# PCB-RS422_485-DB9.net
KiCad netlist of a schematic drawn in EAGLE
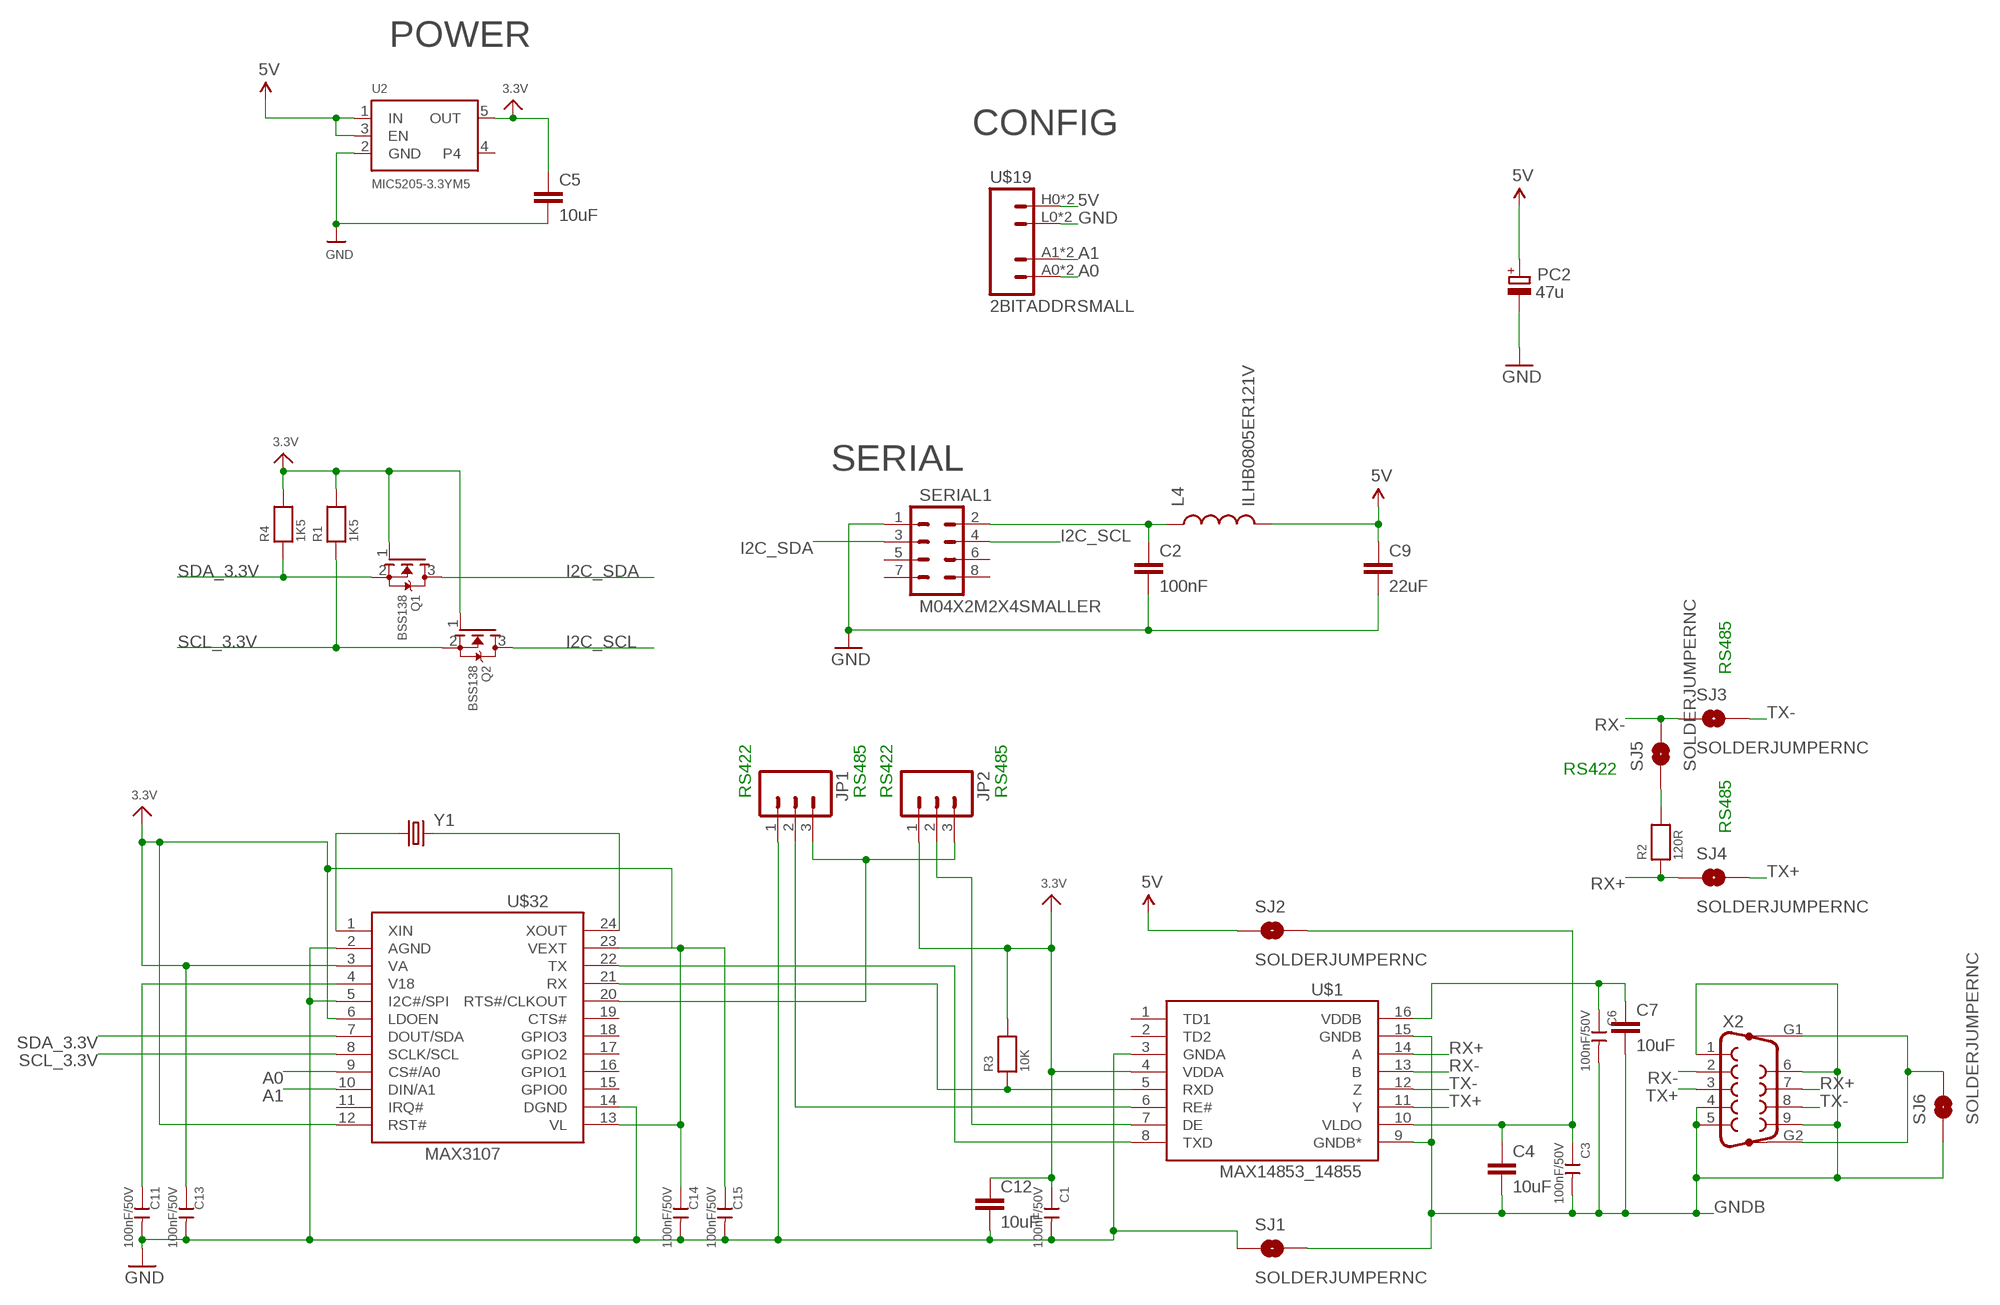
[diagram p0: schematic, sheet 1]

(export (version "E")
  (design (tool "Eeschema 10.0.6"))
  (components
    (comp (ref "C1")
      (value "100nF/50V")
      (footprint "eagle-import:C0603")
      (libsource (lib "eagle-import") (part "CAP-0603"))
    )
    (comp (ref "C2")
      (value "100nF")
      (footprint "eagle-import:0603-CAP")
      (libsource (lib "eagle-import") (part "CAP0603-CAP"))
    )
    (comp (ref "C3")
      (value "100nF/50V")
      (footprint "eagle-import:C0603")
      (libsource (lib "eagle-import") (part "CAP-0603"))
    )
    (comp (ref "C4")
      (value "10uF")
      (footprint "eagle-import:0805")
      (libsource (lib "eagle-import") (part "CAP0805"))
    )
    (comp (ref "C5")
      (value "10uF")
      (footprint "eagle-import:0805")
      (libsource (lib "eagle-import") (part "CAP0805"))
    )
    (comp (ref "C6")
      (value "100nF/50V")
      (footprint "eagle-import:C0603")
      (libsource (lib "eagle-import") (part "CAP-0603"))
    )
    (comp (ref "C7")
      (value "10uF")
      (footprint "eagle-import:0805")
      (libsource (lib "eagle-import") (part "CAP0805"))
    )
    (comp (ref "C9")
      (value "22uF")
      (footprint "eagle-import:0805")
      (libsource (lib "eagle-import") (part "CAP0805"))
    )
    (comp (ref "C11")
      (value "100nF/50V")
      (footprint "eagle-import:C0603")
      (libsource (lib "eagle-import") (part "CAP-0603"))
    )
    (comp (ref "C12")
      (value "10uF")
      (footprint "eagle-import:0805")
      (libsource (lib "eagle-import") (part "CAP0805"))
    )
    (comp (ref "C13")
      (value "100nF/50V")
      (footprint "eagle-import:C0603")
      (libsource (lib "eagle-import") (part "CAP-0603"))
    )
    (comp (ref "C14")
      (value "100nF/50V")
      (footprint "eagle-import:C0603")
      (libsource (lib "eagle-import") (part "CAP-0603"))
    )
    (comp (ref "C15")
      (value "100nF/50V")
      (footprint "eagle-import:C0603")
      (libsource (lib "eagle-import") (part "CAP-0603"))
    )
    (comp (ref "JP1")
      (value "M03LOCK")
      (footprint "eagle-import:1X03_LOCK")
      (libsource (lib "eagle-import") (part "M03LOCK"))
    )
    (comp (ref "JP2")
      (value "M03LOCK")
      (footprint "eagle-import:1X03_LOCK")
      (libsource (lib "eagle-import") (part "M03LOCK"))
    )
    (comp (ref "L4")
      (value "ILHB0805ER121V")
      (footprint "eagle-import:0805")
      (libsource (lib "eagle-import") (part "INDUCTOR0805"))
    )
    (comp (ref "PC2")
      (value "47u")
      (footprint "eagle-import:PANASONIC_D")
      (libsource (lib "eagle-import") (part "CPOL-EUD"))
    )
    (comp (ref "Q1")
      (value "BSS138")
      (footprint "eagle-import:SOT23-R")
      (libsource (lib "eagle-import") (part "MOSFET-NREFLOW"))
    )
    (comp (ref "Q2")
      (value "BSS138")
      (footprint "eagle-import:SOT23-R")
      (libsource (lib "eagle-import") (part "MOSFET-NREFLOW"))
    )
    (comp (ref "R1")
      (value "1K5")
      (footprint "eagle-import:0603")
      (libsource (lib "eagle-import") (part "RESISTOR0603"))
    )
    (comp (ref "R2")
      (value "120R")
      (footprint "eagle-import:0603")
      (libsource (lib "eagle-import") (part "RESISTOR0603"))
    )
    (comp (ref "R3")
      (value "10K")
      (footprint "eagle-import:0603")
      (libsource (lib "eagle-import") (part "RESISTOR0603"))
    )
    (comp (ref "R4")
      (value "1K5")
      (footprint "eagle-import:0603")
      (libsource (lib "eagle-import") (part "RESISTOR0603"))
    )
    (comp (ref "SERIAL1")
      (value "M04X2M2X4SMALLER")
      (footprint "eagle-import:M2X4SMALLER")
      (libsource (lib "eagle-import") (part "M04X2M2X4SMALLER"))
    )
    (comp (ref "SJ1")
      (value "SOLDERJUMPERNC")
      (footprint "eagle-import:SJ_2S")
      (libsource (lib "eagle-import") (part "SOLDERJUMPERNC"))
    )
    (comp (ref "SJ2")
      (value "SOLDERJUMPERNC")
      (footprint "eagle-import:SJ_2S")
      (libsource (lib "eagle-import") (part "SOLDERJUMPERNC"))
    )
    (comp (ref "SJ3")
      (value "SOLDERJUMPERNC")
      (footprint "eagle-import:SJ_2S")
      (libsource (lib "eagle-import") (part "SOLDERJUMPERNC"))
    )
    (comp (ref "SJ4")
      (value "SOLDERJUMPERNC")
      (footprint "eagle-import:SJ_2S")
      (libsource (lib "eagle-import") (part "SOLDERJUMPERNC"))
    )
    (comp (ref "SJ5")
      (value "SOLDERJUMPERNC")
      (footprint "eagle-import:SJ_2S")
      (libsource (lib "eagle-import") (part "SOLDERJUMPERNC"))
    )
    (comp (ref "SJ6")
      (value "SOLDERJUMPERNC")
      (footprint "eagle-import:SJ_2S")
      (libsource (lib "eagle-import") (part "SOLDERJUMPERNC"))
    )
    (comp (ref "U$1")
      (value "MAX14853_14855")
      (footprint "eagle-import:SO-16W")
      (libsource (lib "eagle-import") (part "MAX14853_14855"))
    )
    (comp (ref "U$19")
      (value "2BITADDRSMALL")
      (footprint "eagle-import:2BITADDR_SMALL")
      (libsource (lib "eagle-import") (part "2BITADDRSMALL"))
    )
    (comp (ref "U$32")
      (value "MAX3107")
      (footprint "eagle-import:SSOP24")
      (libsource (lib "eagle-import") (part "MAX3107"))
    )
    (comp (ref "U2")
      (value "MIC5205-3.3YM5")
      (footprint "eagle-import:SOT23-5")
      (libsource (lib "eagle-import") (part "VREG_SOT23-5"))
    )
    (comp (ref "X2")
      (value "F09HP")
      (footprint "eagle-import:F09HP")
      (libsource (lib "eagle-import") (part "F09HP"))
    )
    (comp (ref "Y1")
      (value "CRYSTALHC49US")
      (footprint "eagle-import:HC49US")
      (libsource (lib "eagle-import") (part "CRYSTALHC49US"))
    )
  )
  (nets
    (net (code "1") (name "3.3V") (class "Default")
      (node (ref "C1") (pin "1") (pinfunction "1_1") (pintype "passive"))
      (node (ref "C12") (pin "1") (pinfunction "1_1") (pintype "passive"))
      (node (ref "C13") (pin "1") (pinfunction "1_1") (pintype "passive"))
      (node (ref "C14") (pin "1") (pinfunction "1_1") (pintype "passive"))
      (node (ref "C15") (pin "1") (pinfunction "1_1") (pintype "passive"))
      (node (ref "C5") (pin "1") (pinfunction "1_1") (pintype "passive"))
      (node (ref "JP2") (pin "1") (pinfunction "1_1") (pintype "passive"))
      (node (ref "Q1") (pin "1") (pinfunction "G_1") (pintype "bidirectional"))
      (node (ref "Q2") (pin "1") (pinfunction "G_1") (pintype "bidirectional"))
      (node (ref "R1") (pin "2") (pinfunction "2_2") (pintype "passive"))
      (node (ref "R3") (pin "2") (pinfunction "2_2") (pintype "passive"))
      (node (ref "R4") (pin "2") (pinfunction "2_2") (pintype "passive"))
      (node (ref "U$1") (pin "4") (pinfunction "VDDA_4") (pintype "power_in"))
      (node (ref "U$32") (pin "12") (pinfunction "RST#_12") (pintype "input"))
      (node (ref "U$32") (pin "13") (pinfunction "VL_13") (pintype "power_in"))
      (node (ref "U$32") (pin "23") (pinfunction "VEXT_23") (pintype "power_in"))
      (node (ref "U$32") (pin "3") (pinfunction "VA_3") (pintype "power_in"))
      (node (ref "U$32") (pin "6") (pinfunction "LDOEN_6") (pintype "input"))
      (node (ref "U2") (pin "5") (pinfunction "OUT_5") (pintype "bidirectional"))
    )
    (net (code "2") (name "5V") (class "Default")
      (node (ref "C9") (pin "1") (pinfunction "1_1") (pintype "passive"))
      (node (ref "L4") (pin "2") (pinfunction "2_2") (pintype "passive"))
      (node (ref "PC2") (pin "+") (pinfunction "+_+") (pintype "passive"))
      (node (ref "SJ2") (pin "1") (pinfunction "1_1") (pintype "passive"))
      (node (ref "U$19") (pin "H0") (pinfunction "VCC_H0") (pintype "passive"))
      (node (ref "U$19") (pin "H1") (pinfunction "VCC_H1") (pintype "passive"))
      (node (ref "U2") (pin "1") (pinfunction "IN_1") (pintype "bidirectional"))
      (node (ref "U2") (pin "3") (pinfunction "EN_3") (pintype "bidirectional"))
    )
    (net (code "3") (name "A0") (class "Default")
      (node (ref "U$19") (pin "A0") (pinfunction "A1_A0") (pintype "passive"))
      (node (ref "U$19") (pin "AS0") (pinfunction "A1_AS0") (pintype "passive"))
      (node (ref "U$32") (pin "9") (pinfunction "CS#/A0_9") (pintype "input"))
    )
    (net (code "4") (name "A1") (class "Default")
      (node (ref "U$19") (pin "A1") (pinfunction "A2_A1") (pintype "passive"))
      (node (ref "U$19") (pin "AS1") (pinfunction "A2_AS1") (pintype "passive"))
      (node (ref "U$32") (pin "10") (pinfunction "DIN/A1_10") (pintype "input"))
    )
    (net (code "5") (name "GND") (class "Default")
      (node (ref "C1") (pin "2") (pinfunction "2_2") (pintype "passive"))
      (node (ref "C11") (pin "2") (pinfunction "2_2") (pintype "passive"))
      (node (ref "C12") (pin "2") (pinfunction "2_2") (pintype "passive"))
      (node (ref "C13") (pin "2") (pinfunction "2_2") (pintype "passive"))
      (node (ref "C14") (pin "2") (pinfunction "2_2") (pintype "passive"))
      (node (ref "C15") (pin "2") (pinfunction "2_2") (pintype "passive"))
      (node (ref "C2") (pin "2") (pinfunction "2_2") (pintype "passive"))
      (node (ref "C5") (pin "2") (pinfunction "2_2") (pintype "passive"))
      (node (ref "C9") (pin "2") (pinfunction "2_2") (pintype "passive"))
      (node (ref "JP1") (pin "1") (pinfunction "1_1") (pintype "passive"))
      (node (ref "PC2") (pin "-") (pinfunction "-_-") (pintype "passive"))
      (node (ref "SERIAL1") (pin "1") (pinfunction "1_1") (pintype "passive"))
      (node (ref "SJ1") (pin "1") (pinfunction "1_1") (pintype "passive"))
      (node (ref "U$1") (pin "3") (pinfunction "GNDA_3") (pintype "power_in"))
      (node (ref "U$19") (pin "L0") (pinfunction "GND_L0") (pintype "passive"))
      (node (ref "U$19") (pin "L1") (pinfunction "GND_L1") (pintype "passive"))
      (node (ref "U$32") (pin "14") (pinfunction "DGND_14") (pintype "power_in"))
      (node (ref "U$32") (pin "2") (pinfunction "AGND_2") (pintype "power_in"))
      (node (ref "U$32") (pin "5") (pinfunction "I2C#/SPI_5") (pintype "input"))
      (node (ref "U2") (pin "2") (pinfunction "GND_2") (pintype "bidirectional"))
    )
    (net (code "6") (name "GNDB") (class "Default")
      (node (ref "C3") (pin "2") (pinfunction "2_2") (pintype "passive"))
      (node (ref "C4") (pin "2") (pinfunction "2_2") (pintype "passive"))
      (node (ref "C6") (pin "2") (pinfunction "2_2") (pintype "passive"))
      (node (ref "C7") (pin "2") (pinfunction "2_2") (pintype "passive"))
      (node (ref "SJ1") (pin "2") (pinfunction "2_2") (pintype "passive"))
      (node (ref "SJ6") (pin "1") (pinfunction "1_1") (pintype "passive"))
      (node (ref "U$1") (pin "15") (pinfunction "GNDB_15") (pintype "power_in"))
      (node (ref "U$1") (pin "9") (pinfunction "GNDB*_9") (pintype "power_in"))
      (node (ref "X2") (pin "1") (pinfunction "1_1") (pintype "passive"))
      (node (ref "X2") (pin "4") (pinfunction "4_4") (pintype "passive"))
      (node (ref "X2") (pin "5") (pinfunction "5_5") (pintype "passive"))
      (node (ref "X2") (pin "6") (pinfunction "6_6") (pintype "passive"))
      (node (ref "X2") (pin "9") (pinfunction "9_9") (pintype "passive"))
    )
    (net (code "7") (name "I2C_SCL") (class "Default")
      (node (ref "Q2") (pin "3") (pinfunction "D_3") (pintype "bidirectional"))
      (node (ref "SERIAL1") (pin "4") (pinfunction "4_4") (pintype "passive"))
    )
    (net (code "8") (name "I2C_SDA") (class "Default")
      (node (ref "Q1") (pin "3") (pinfunction "D_3") (pintype "bidirectional"))
      (node (ref "SERIAL1") (pin "3") (pinfunction "3_3") (pintype "passive"))
    )
    (net (code "9") (name "Net-(C2-Pad1)") (class "Default")
      (node (ref "C2") (pin "1") (pinfunction "1_1") (pintype "passive"))
      (node (ref "L4") (pin "1") (pinfunction "1_1") (pintype "passive"))
      (node (ref "SERIAL1") (pin "2") (pinfunction "2_2") (pintype "passive"))
    )
    (net (code "10") (name "Net-(R2-Pad2)") (class "Default")
      (node (ref "R2") (pin "2") (pinfunction "2_2") (pintype "passive"))
      (node (ref "SJ5") (pin "1") (pinfunction "1_1") (pintype "passive"))
    )
    (net (code "11") (name "Net-(SJ6-Pad2)") (class "Default")
      (node (ref "SJ6") (pin "2") (pinfunction "2_2") (pintype "passive"))
      (node (ref "X2") (pin "G1") (pinfunction "G1_G1") (pintype "passive"))
      (node (ref "X2") (pin "G2") (pinfunction "G2_G2") (pintype "passive"))
    )
    (net (code "12") (name "Net-(U$1-DE)") (class "Default")
      (node (ref "JP2") (pin "2") (pinfunction "2_2") (pintype "passive"))
      (node (ref "U$1") (pin "7") (pinfunction "DE_7") (pintype "input"))
    )
    (net (code "13") (name "Net-(U$1-RE#)") (class "Default")
      (node (ref "JP1") (pin "2") (pinfunction "2_2") (pintype "passive"))
      (node (ref "U$1") (pin "6") (pinfunction "RE#_6") (pintype "input"))
    )
    (net (code "14") (name "Net-(U$1-RXD)") (class "Default")
      (node (ref "R3") (pin "1") (pinfunction "1_1") (pintype "passive"))
      (node (ref "U$1") (pin "5") (pinfunction "RXD_5") (pintype "output"))
      (node (ref "U$32") (pin "21") (pinfunction "RX_21") (pintype "input"))
    )
    (net (code "15") (name "Net-(U$1-TXD)") (class "Default")
      (node (ref "U$1") (pin "8") (pinfunction "TXD_8") (pintype "input"))
      (node (ref "U$32") (pin "22") (pinfunction "TX_22") (pintype "output"))
    )
    (net (code "16") (name "Net-(U$1-VDDB)") (class "Default")
      (node (ref "C6") (pin "1") (pinfunction "1_1") (pintype "passive"))
      (node (ref "C7") (pin "1") (pinfunction "1_1") (pintype "passive"))
      (node (ref "U$1") (pin "16") (pinfunction "VDDB_16") (pintype "output"))
    )
    (net (code "17") (name "Net-(U$1-VLDO)") (class "Default")
      (node (ref "C3") (pin "1") (pinfunction "1_1") (pintype "passive"))
      (node (ref "C4") (pin "1") (pinfunction "1_1") (pintype "passive"))
      (node (ref "SJ2") (pin "2") (pinfunction "2_2") (pintype "passive"))
      (node (ref "U$1") (pin "10") (pinfunction "VLDO_10") (pintype "power_in"))
    )
    (net (code "18") (name "Net-(U$32-RTS#{slash}CLKOUT)") (class "Default")
      (node (ref "JP1") (pin "3") (pinfunction "3_3") (pintype "passive"))
      (node (ref "JP2") (pin "3") (pinfunction "3_3") (pintype "passive"))
      (node (ref "U$32") (pin "20") (pinfunction "RTS#/CLKOUT_20") (pintype "bidirectional"))
    )
    (net (code "19") (name "Net-(U$32-V18)") (class "Default")
      (node (ref "C11") (pin "1") (pinfunction "1_1") (pintype "passive"))
      (node (ref "U$32") (pin "4") (pinfunction "V18_4") (pintype "output"))
    )
    (net (code "20") (name "Net-(U$32-XIN)") (class "Default")
      (node (ref "U$32") (pin "1") (pinfunction "XIN_1") (pintype "bidirectional"))
      (node (ref "Y1") (pin "1") (pinfunction "1_1") (pintype "passive"))
    )
    (net (code "21") (name "Net-(U$32-XOUT)") (class "Default")
      (node (ref "U$32") (pin "24") (pinfunction "XOUT_24") (pintype "bidirectional"))
      (node (ref "Y1") (pin "2") (pinfunction "2_2") (pintype "passive"))
    )
    (net (code "22") (name "RX+") (class "Default")
      (node (ref "R2") (pin "1") (pinfunction "1_1") (pintype "passive"))
      (node (ref "SJ4") (pin "1") (pinfunction "1_1") (pintype "passive"))
      (node (ref "U$1") (pin "14") (pinfunction "A_14") (pintype "input"))
      (node (ref "X2") (pin "7") (pinfunction "7_7") (pintype "passive"))
    )
    (net (code "23") (name "RX-") (class "Default")
      (node (ref "SJ3") (pin "1") (pinfunction "1_1") (pintype "passive"))
      (node (ref "SJ5") (pin "2") (pinfunction "2_2") (pintype "passive"))
      (node (ref "U$1") (pin "13") (pinfunction "B_13") (pintype "input"))
      (node (ref "X2") (pin "2") (pinfunction "2_2") (pintype "passive"))
    )
    (net (code "24") (name "SCL_3.3V") (class "Default")
      (node (ref "Q2") (pin "2") (pinfunction "S_2") (pintype "bidirectional"))
      (node (ref "R1") (pin "1") (pinfunction "1_1") (pintype "passive"))
      (node (ref "U$32") (pin "8") (pinfunction "SCLK/SCL_8") (pintype "input"))
    )
    (net (code "25") (name "SDA_3.3V") (class "Default")
      (node (ref "Q1") (pin "2") (pinfunction "S_2") (pintype "bidirectional"))
      (node (ref "R4") (pin "1") (pinfunction "1_1") (pintype "passive"))
      (node (ref "U$32") (pin "7") (pinfunction "DOUT/SDA_7") (pintype "bidirectional"))
    )
    (net (code "26") (name "TX+") (class "Default")
      (node (ref "SJ4") (pin "2") (pinfunction "2_2") (pintype "passive"))
      (node (ref "U$1") (pin "11") (pinfunction "Y_11") (pintype "output"))
      (node (ref "X2") (pin "3") (pinfunction "3_3") (pintype "passive"))
    )
    (net (code "27") (name "TX-") (class "Default")
      (node (ref "SJ3") (pin "2") (pinfunction "2_2") (pintype "passive"))
      (node (ref "U$1") (pin "12") (pinfunction "Z_12") (pintype "output"))
      (node (ref "X2") (pin "8") (pinfunction "8_8") (pintype "passive"))
    )
    (net (code "28") (name "unconnected-(SERIAL1-Pad5)") (class "Default")
      (node (ref "SERIAL1") (pin "5") (pinfunction "5_5") (pintype "passive"))
    )
    (net (code "29") (name "unconnected-(SERIAL1-Pad6)") (class "Default")
      (node (ref "SERIAL1") (pin "6") (pinfunction "6_6") (pintype "passive"))
    )
    (net (code "30") (name "unconnected-(SERIAL1-Pad7)") (class "Default")
      (node (ref "SERIAL1") (pin "7") (pinfunction "7_7") (pintype "passive"))
    )
    (net (code "31") (name "unconnected-(SERIAL1-Pad8)") (class "Default")
      (node (ref "SERIAL1") (pin "8") (pinfunction "8_8") (pintype "passive"))
    )
    (net (code "32") (name "unconnected-(U$1-TD1-Pad1)") (class "Default")
      (node (ref "U$1") (pin "1") (pinfunction "TD1_1") (pintype "output"))
    )
    (net (code "33") (name "unconnected-(U$1-TD2-Pad2)") (class "Default")
      (node (ref "U$1") (pin "2") (pinfunction "TD2_2") (pintype "output"))
    )
    (net (code "34") (name "unconnected-(U$32-CTS#-Pad19)") (class "Default")
      (node (ref "U$32") (pin "19") (pinfunction "CTS#_19") (pintype "bidirectional"))
    )
    (net (code "35") (name "unconnected-(U$32-GPIO0-Pad15)") (class "Default")
      (node (ref "U$32") (pin "15") (pinfunction "GPIO0_15") (pintype "bidirectional"))
    )
    (net (code "36") (name "unconnected-(U$32-GPIO1-Pad16)") (class "Default")
      (node (ref "U$32") (pin "16") (pinfunction "GPIO1_16") (pintype "bidirectional"))
    )
    (net (code "37") (name "unconnected-(U$32-GPIO2-Pad17)") (class "Default")
      (node (ref "U$32") (pin "17") (pinfunction "GPIO2_17") (pintype "bidirectional"))
    )
    (net (code "38") (name "unconnected-(U$32-GPIO3-Pad18)") (class "Default")
      (node (ref "U$32") (pin "18") (pinfunction "GPIO3_18") (pintype "bidirectional"))
    )
    (net (code "39") (name "unconnected-(U$32-IRQ#-Pad11)") (class "Default")
      (node (ref "U$32") (pin "11") (pinfunction "IRQ#_11") (pintype "output"))
    )
    (net (code "40") (name "unconnected-(U2-P4-Pad4)") (class "Default")
      (node (ref "U2") (pin "4") (pinfunction "P4_4") (pintype "bidirectional"))
    )
  )
)
